# TIDA-010954-Power.net
KiCad netlist of a schematic drawn in Altium Designer
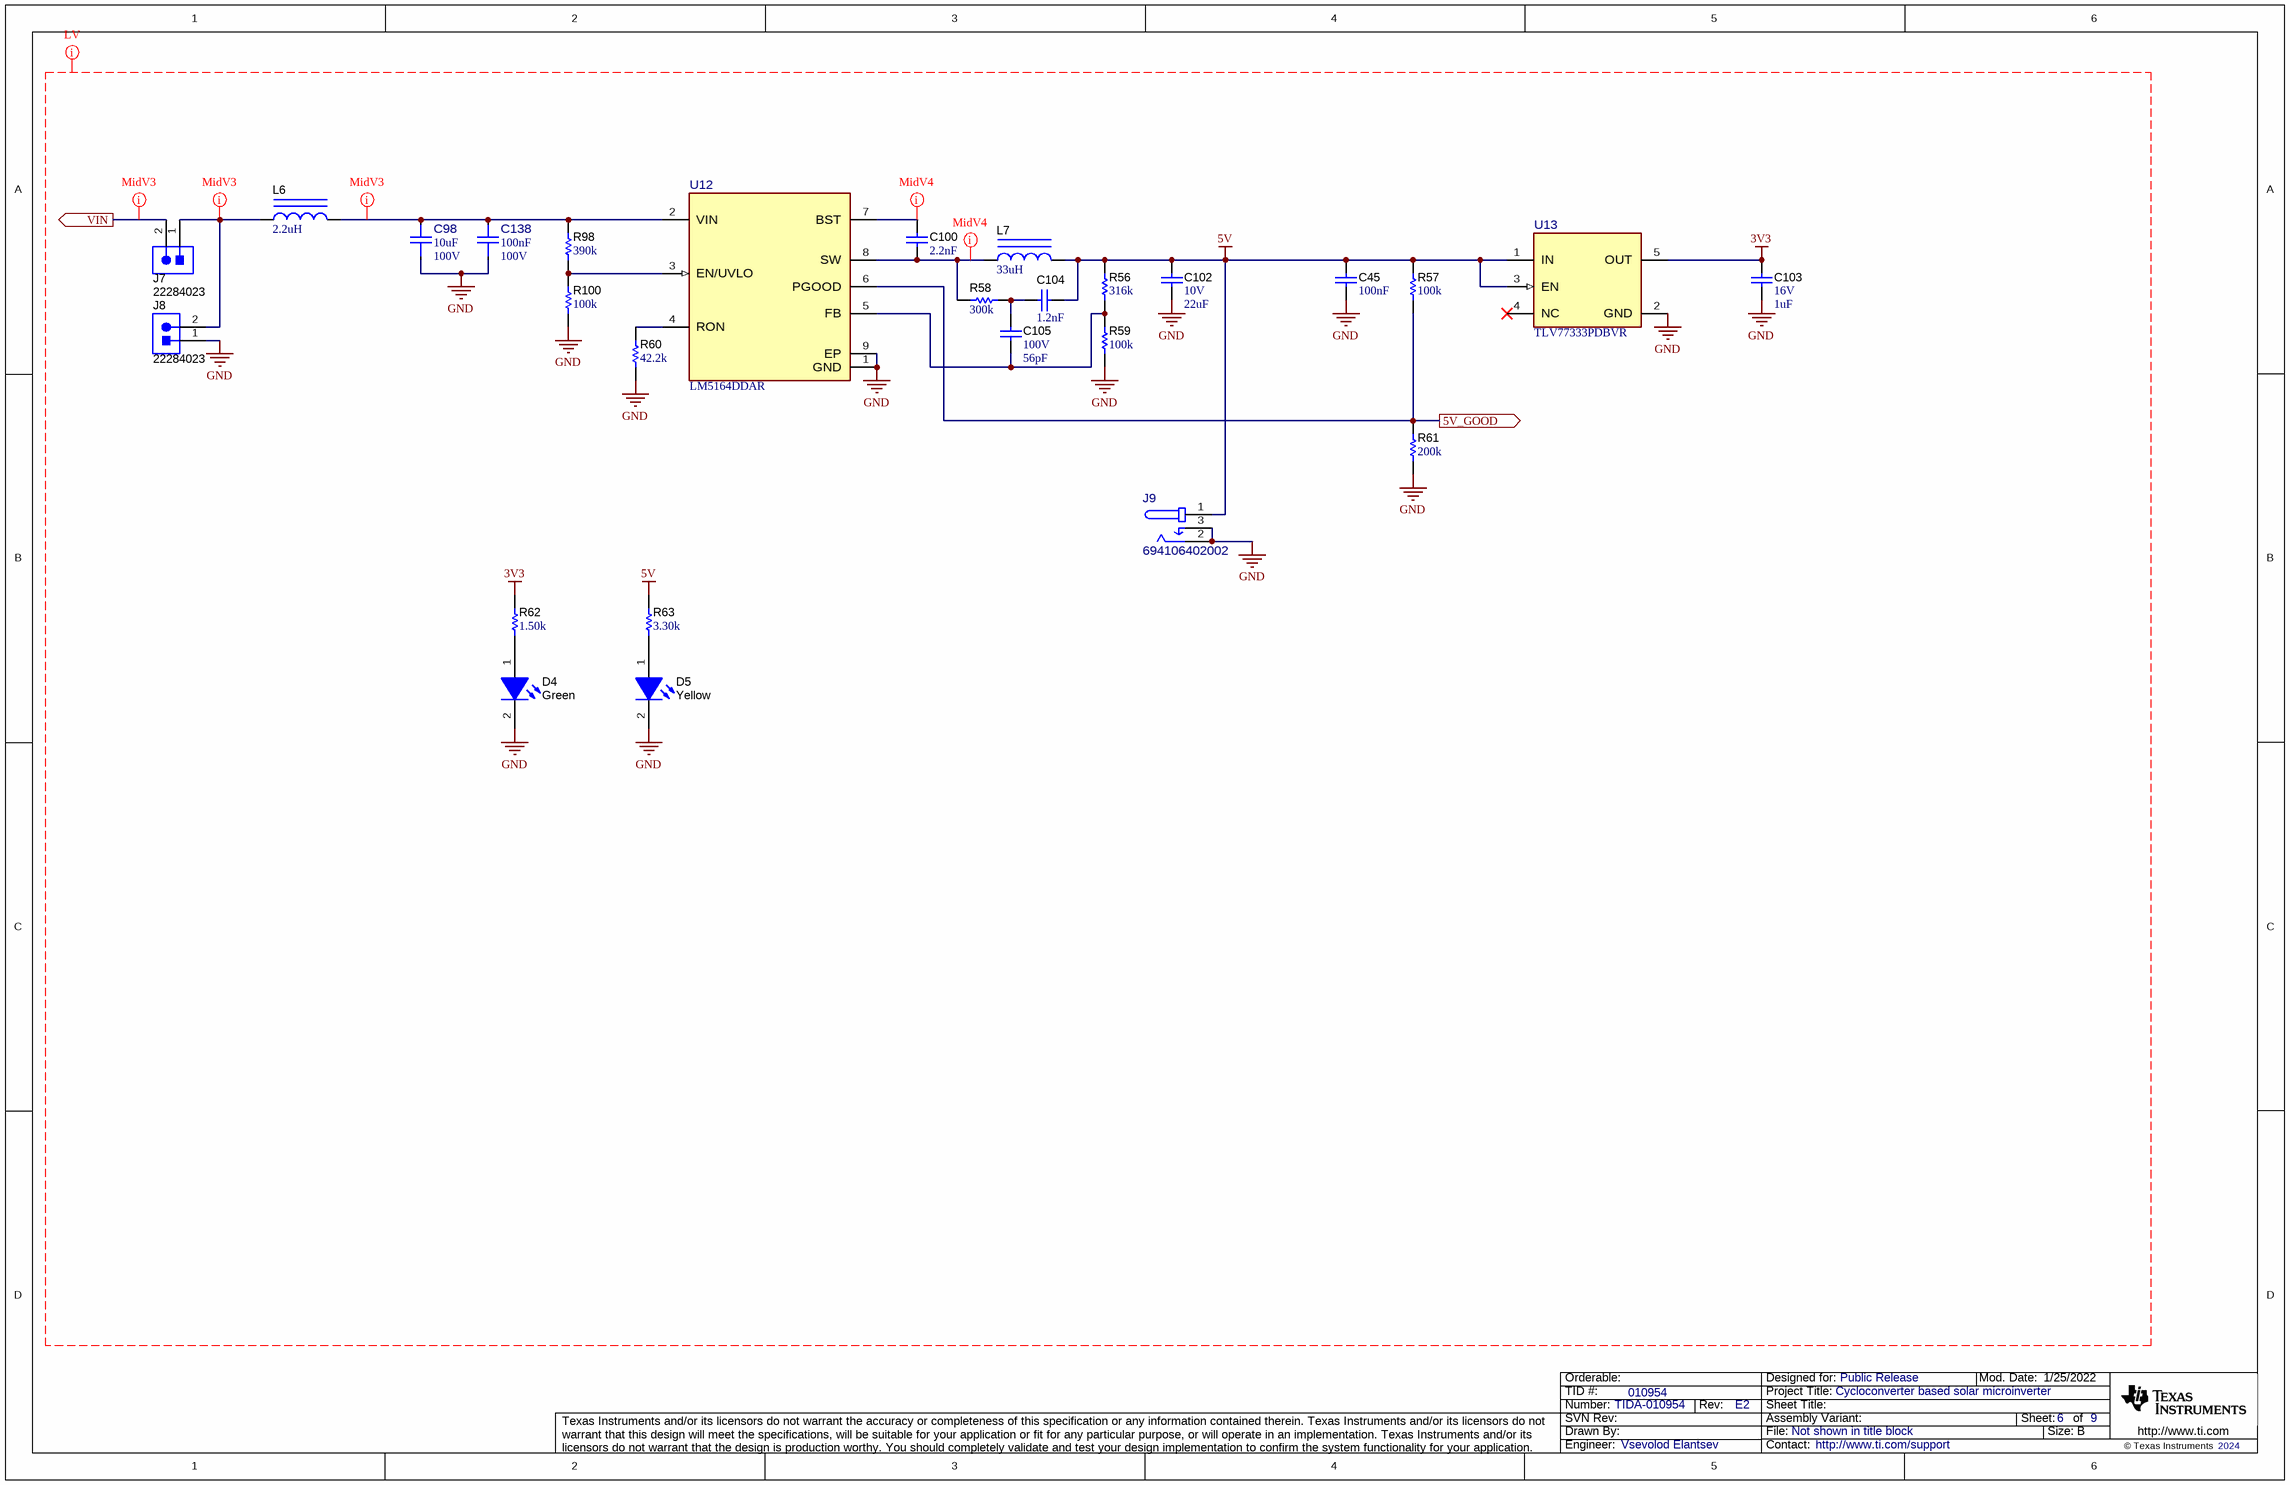
[diagram p0: TIDA-010954-Power.SchDoc]

(export (version "E")
  (design (tool "Eeschema 10.0.6"))
  (components
    (comp (ref "C45")
      (value "CGA3E2X7R1E104K080AA")
      (footprint "0603")
      (description "CAP, CERM, 0.1 uF, 25 V, +/- 10%, X7R, AEC-Q200 Grade 1, 0603")
      (fields
        (field (name "MANUFACTURER") "TDK")
        (field (name "CAP_F") "100nF")
        (field (name "PUBLISHER") "Texas Instruments")
      )
      (libsource (lib "Altium Vault - TI") (part "Capacitor"))
    )
    (comp (ref "C98")
      (value "GRM32EC72A106KE05L")
      (footprint "FP-GRM32EC72A106KE05L_1210-MFG")
      (description "10µF ±10% 100V Ceramic Capacitor X7S 1210 (3225 Metric)")
      (fields
        (field (name "VALUEDISPLAYED") "10uF")
        (field (name "MANUFACTURER") "Murata")
        (field (name "VDC_V") "100V")
      )
      (libsource (lib "Altium Vault - TI") (part "SYM-CC0402JRNPO9BN161"))
    )
    (comp (ref "C100")
      (value "C0603C222K5RAC")
      (footprint "0603")
      (description "CAP, CERM, 2200 pF, 50 V, +/- 10%, X7R, 0603")
      (fields
        (field (name "MANUFACTURER") "Kemet")
        (field (name "CAP_F") "2.2nF")
        (field (name "PUBLISHER") "Texas Instruments")
      )
      (libsource (lib "Altium Vault - TI") (part "Capacitor"))
    )
    (comp (ref "C102")
      (value "GRM31CR71A226KE15L")
      (footprint "1206_180")
      (description "CAP, CERM, 22 uF, 10 V, +/- 10%, X7R, 1206")
      (fields
        (field (name "MANUFACTURER") "MuRata")
        (field (name "VDC_V") "10V")
        (field (name "VALUEDISPLAYED") "22uF")
        (field (name "PUBLISHER") "Texas Instruments")
      )
      (libsource (lib "Altium Vault - TI") (part "Capacitor"))
    )
    (comp (ref "C103")
      (value "GRM185R61C105KE44D")
      (footprint "0603")
      (description "CAP, CERM, 1 uF, 16 V, +/- 10%, X5R, 0603")
      (fields
        (field (name "MANUFACTURER") "MuRata")
        (field (name "VDC_V") "16V")
        (field (name "VALUEDISPLAYED") "1uF")
        (field (name "PUBLISHER") "Texas Instruments")
      )
      (libsource (lib "Altium Vault - TI") (part "Capacitor"))
    )
    (comp (ref "C104")
      (value "GRM188R72A122KA01D")
      (footprint "0603")
      (description "CAP, CERM, 1200 pF, 100 V, +/- 10%, X7R, 0603")
      (fields
        (field (name "MANUFACTURER") "MuRata")
        (field (name "CAP_F") "1.2nF")
        (field (name "PUBLISHER") "Texas Instruments")
      )
      (libsource (lib "Altium Vault - TI") (part "Capacitor"))
    )
    (comp (ref "C105")
      (value "GRM1885C2A560JA01D")
      (footprint "0603")
      (description "CAP, CERM, 56 pF, 100 V, +/- 5%, C0G/NP0, 0603")
      (fields
        (field (name "MANUFACTURER") "MuRata")
        (field (name "VDC_V") "100V")
        (field (name "VALUEDISPLAYED") "56pF")
        (field (name "PUBLISHER") "Texas Instruments")
      )
      (libsource (lib "Altium Vault - TI") (part "Capacitor"))
    )
    (comp (ref "C138")
      (value "GRM188R72A104KA35J")
      (footprint "FP-GRM188R72A104KA35J_0603-MFG")
      (description "Chip Multilayer Ceramic Capacitors for General Purpose, 0603, 0.10uF, X7R, 15%, 10%, 100V")
      (fields
        (field (name "CAP_F") "100nF")
        (field (name "MANUFACTURER") "Murata")
        (field (name "VDC_V") "100V")
      )
      (libsource (lib "Altium Vault - TI") (part "SYM-GRM188R72A104KA35J"))
    )
    (comp (ref "D4")
      (value "Green")
      (footprint "APT1608_Green")
      (description "LED, Green, SMD")
      (fields (field (name "MANUFACTURER") "Kingbright") (field (name "PARTNUMBER") "APT1608MGC"))
      (libsource (lib "Altium Vault - TI") (part "LED"))
    )
    (comp (ref "D5")
      (value "Yellow")
      (footprint "APT1608_Yellow")
      (description "LED, Yellow, SMD")
      (fields (field (name "MANUFACTURER") "Kingbright") (field (name "PARTNUMBER") "APT1608SYCK"))
      (libsource (lib "Altium Vault - TI") (part "LED"))
    )
    (comp (ref "J7")
      (value "22284023")
      (footprint "Molex_0022284023")
      (description "Header, 2.54mm, 2x1, Tin, TH")
      (fields (field (name "MANUFACTURER") "Molex") (field (name "PUBLISHER") "Texas Instruments"))
      (libsource (lib "") (part "Header_2x1_1"))
    )
    (comp (ref "J8")
      (value "22284023")
      (footprint "Molex_0022284023")
      (description "Header, 2.54mm, 2x1, Tin, TH")
      (fields (field (name "MANUFACTURER") "Molex") (field (name "PUBLISHER") "Texas Instruments"))
      (libsource (lib "Altium Vault - TI") (part "Header_2x1"))
    )
    (comp (ref "J9")
      (value "694106402002")
      (footprint "FP-694106402002_CONN_PWR_10MM7_9MM0-MFG")
      (description "Power Barrel Connector Jack 2.10mm ID (0.083\"), 5.50mm OD (0.217\") Through Hole")
      (fields
        (field (name "MANUFACTURER") "Wurth Electronics")
        (field (name "DIGIKEY PART NUMBER") "732-5931-ND")
      )
      (libsource (lib "Altium Vault - TI") (part "SYM-694106402002"))
    )
    (comp (ref "L6")
      (value "LQM21PN2R2MGS")
      (footprint "0805_HV")
      (description "Inductor, Multilayer, Ferrite, 2.2 uH, 0.95 A, 0.18 ohm, SMD")
      (fields
        (field (name "MANUFACTURER") "MuRata")
        (field (name "VALUEDISPLAYED") "2.2uH")
        (field (name "PUBLISHER") "Texas Instruments")
      )
      (libsource (lib "Altium Vault - TI") (part "Inductor_Iron"))
    )
    (comp (ref "L7")
      (value "SRR1210-330M")
      (footprint "SRR1210")
      (description "Inductor, Drum Core, Ferrite, 33 uH, 3.7 A, 0.052 ohm, SMD")
      (fields
        (field (name "MANUFACTURER") "Bourns")
        (field (name "VALUEDISPLAYED") "33uH")
        (field (name "PUBLISHER") "Texas Instruments")
      )
      (libsource (lib "Altium Vault - TI") (part "Inductor_Iron"))
    )
    (comp (ref "R56")
      (value "RC0603FR-07316KL")
      (footprint "0603")
      (description "RES, 316 k, 1%, 0.1 W, 0603")
      (fields (field (name "MANUFACTURER") "Yageo") (field (name "VALUEDISPLAYED") "316k"))
      (libsource (lib "Altium Vault - TI") (part "Resistor"))
    )
    (comp (ref "R57")
      (value "RC0603FR-07100KL")
      (footprint "0603")
      (description "RES, 100 k, 1%, 0.1 W, 0603")
      (fields (field (name "MANUFACTURER") "Yageo") (field (name "VALUEDISPLAYED") "100k"))
      (libsource (lib "Altium Vault - TI") (part "Resistor"))
    )
    (comp (ref "R58")
      (value "CRCW0805300KJNEA")
      (footprint "0805_HV")
      (description "RES, 300 k, 5%, 0.125 W, AEC-Q200 Grade 0, 0805")
      (fields (field (name "MANUFACTURER") "Vishay-Dale") (field (name "VALUEDISPLAYED") "300k"))
      (libsource (lib "Altium Vault - TI") (part "Resistor"))
    )
    (comp (ref "R59")
      (value "RC0603FR-07100KL")
      (footprint "0603")
      (description "RES, 100 k, 1%, 0.1 W, 0603")
      (fields (field (name "MANUFACTURER") "Yageo") (field (name "VALUEDISPLAYED") "100k"))
      (libsource (lib "Altium Vault - TI") (part "Resistor"))
    )
    (comp (ref "R60")
      (value "RC0603FR-0742K2L")
      (footprint "0603")
      (description "RES, 42.2 k, 1%, 0.1 W, 0603")
      (fields (field (name "MANUFACTURER") "Yageo") (field (name "VALUEDISPLAYED") "42.2k"))
      (libsource (lib "Altium Vault - TI") (part "Resistor"))
    )
    (comp (ref "R61")
      (value "RC0603FR-07200KL")
      (footprint "0603")
      (description "RES, 200 k, 1%, 0.1 W, 0603")
      (fields (field (name "MANUFACTURER") "Yageo") (field (name "VALUEDISPLAYED") "200k"))
      (libsource (lib "Altium Vault - TI") (part "Resistor"))
    )
    (comp (ref "R62")
      (value "RC0603FR-071K5L")
      (footprint "0603")
      (description "RES, 1.50 k, 1%, 0.1 W, 0603")
      (fields (field (name "MANUFACTURER") "Yageo") (field (name "VALUEDISPLAYED") "1.50k"))
      (libsource (lib "Altium Vault - TI") (part "Resistor"))
    )
    (comp (ref "R63")
      (value "RC0603FR-073K3L")
      (footprint "0603")
      (description "RES, 3.30 k, 1%, 0.1 W, 0603")
      (fields (field (name "VALUEDISPLAYED") "3.30k") (field (name "MANUFACTURER") "Yageo"))
      (libsource (lib "Altium Vault - TI") (part "Resistor"))
    )
    (comp (ref "R98")
      (value "CRCW0805390KJNEA")
      (footprint "0805_HV")
      (description "RES, 390 k, 5%, 0.125 W, AEC-Q200 Grade 0, 0805")
      (fields (field (name "MANUFACTURER") "Vishay-Dale") (field (name "VALUEDISPLAYED") "390k"))
      (libsource (lib "Altium Vault - TI") (part "Resistor"))
    )
    (comp (ref "R100")
      (value "RC0603FR-07100KL")
      (footprint "0603")
      (description "RES, 100 k, 1%, 0.1 W, 0603")
      (fields (field (name "MANUFACTURER") "Yageo") (field (name "VALUEDISPLAYED") "100k"))
      (libsource (lib "Altium Vault - TI") (part "Resistor"))
    )
    (comp (ref "U12")
      (value "LM5164DDAR")
      (footprint "DDA0008E-MFG")
      (fields
        (field (name "PARTNUMBER") "LM5164DDAR")
        (field (name "MOUSER PART NUMBER") "595-LM5164DDAR")
        (field (name "MANUFACTURER") "Texas Instruments")
        (field (name "DIGIKEY PART NUMBER") "296-LM5164DDARCT-ND")
      )
      (libsource (lib "Altium Vault - TI") (part "SYM-LM5164DDAR"))
    )
    (comp (ref "U13")
      (value "TLV77333PDBVR")
      (footprint "DBV0005A-MFG")
      (description "300-mA, Small-Size, High-PSRR LDO")
      (fields (field (name "MANUFACTURER") "Texas Instruments") (field (name "PARTNUMBER") "TLV77333PDBVR"))
      (libsource (lib "Altium Vault - TI") (part "SYM-TLV77333PDBVR"))
    )
  )
  (nets
    (net (code "1") (name "/5V_GOOD") (class "Default")
      (node (ref "R57") (pin "1") (pinfunction "1_1") (pintype "passive"))
      (node (ref "R61") (pin "2") (pinfunction "2_2") (pintype "passive"))
      (node (ref "U12") (pin "6") (pinfunction "PGOOD_6") (pintype "open_collector"))
    )
    (net (code "2") (name "/VIN") (class "Default")
      (node (ref "J7") (pin "2") (pinfunction "2_2") (pintype "passive"))
    )
    (net (code "3") (name "3V3") (class "Default")
      (node (ref "C103") (pin "1") (pinfunction "1_1") (pintype "passive"))
      (node (ref "R62") (pin "2") (pinfunction "2_2") (pintype "passive"))
      (node (ref "U13") (pin "5") (pinfunction "OUT_5") (pintype "passive"))
    )
    (net (code "4") (name "5V") (class "Default")
      (node (ref "C102") (pin "1") (pinfunction "1_1") (pintype "passive"))
      (node (ref "C104") (pin "1") (pinfunction "1_1") (pintype "passive"))
      (node (ref "C45") (pin "2") (pinfunction "2_2") (pintype "passive"))
      (node (ref "J9") (pin "1") (pinfunction "1_1") (pintype "passive"))
      (node (ref "L7") (pin "2") (pinfunction "2_2") (pintype "passive"))
      (node (ref "R56") (pin "2") (pinfunction "2_2") (pintype "passive"))
      (node (ref "R57") (pin "2") (pinfunction "2_2") (pintype "passive"))
      (node (ref "R63") (pin "2") (pinfunction "2_2") (pintype "passive"))
      (node (ref "U13") (pin "1") (pinfunction "IN_1") (pintype "power_in"))
      (node (ref "U13") (pin "3") (pinfunction "EN_3") (pintype "input"))
    )
    (net (code "5") (name "GND") (class "Default")
      (node (ref "C102") (pin "2") (pinfunction "2_2") (pintype "passive"))
      (node (ref "C103") (pin "2") (pinfunction "2_2") (pintype "passive"))
      (node (ref "C138") (pin "1") (pinfunction "1_1") (pintype "passive"))
      (node (ref "C45") (pin "1") (pinfunction "1_1") (pintype "passive"))
      (node (ref "C98") (pin "1") (pinfunction "1_1") (pintype "passive"))
      (node (ref "D4") (pin "2") (pinfunction "K_2") (pintype "passive"))
      (node (ref "D5") (pin "2") (pinfunction "K_2") (pintype "passive"))
      (node (ref "J8") (pin "1") (pinfunction "1_1") (pintype "passive"))
      (node (ref "J9") (pin "2") (pinfunction "2_2") (pintype "passive"))
      (node (ref "J9") (pin "3") (pinfunction "3_3") (pintype "passive"))
      (node (ref "R100") (pin "1") (pinfunction "1_1") (pintype "passive"))
      (node (ref "R59") (pin "1") (pinfunction "1_1") (pintype "passive"))
      (node (ref "R60") (pin "1") (pinfunction "1_1") (pintype "passive"))
      (node (ref "R61") (pin "1") (pinfunction "1_1") (pintype "passive"))
      (node (ref "U12") (pin "1") (pinfunction "GND_1") (pintype "power_in"))
      (node (ref "U12") (pin "9") (pinfunction "EP_9") (pintype "passive"))
      (node (ref "U13") (pin "2") (pinfunction "GND_2") (pintype "power_in"))
    )
    (net (code "6") (name "Net-(C104-Pad2)") (class "Default")
      (node (ref "C104") (pin "2") (pinfunction "2_2") (pintype "passive"))
      (node (ref "C105") (pin "1") (pinfunction "1_1") (pintype "passive"))
      (node (ref "R58") (pin "2") (pinfunction "2_2") (pintype "passive"))
    )
    (net (code "7") (name "Net-(D4-A)") (class "Default")
      (node (ref "D4") (pin "1") (pinfunction "A_1") (pintype "passive"))
      (node (ref "R62") (pin "1") (pinfunction "1_1") (pintype "passive"))
    )
    (net (code "8") (name "Net-(D5-A)") (class "Default")
      (node (ref "D5") (pin "1") (pinfunction "A_1") (pintype "passive"))
      (node (ref "R63") (pin "1") (pinfunction "1_1") (pintype "passive"))
    )
    (net (code "9") (name "Net-(J7-Pad1)") (class "Default")
      (node (ref "J7") (pin "1") (pinfunction "1_1") (pintype "passive"))
      (node (ref "J8") (pin "2") (pinfunction "2_2") (pintype "passive"))
      (node (ref "L6") (pin "1") (pinfunction "1_1") (pintype "passive"))
    )
    (net (code "10") (name "Net-(U12-BST)") (class "Default")
      (node (ref "C100") (pin "1") (pinfunction "1_1") (pintype "passive"))
      (node (ref "U12") (pin "7") (pinfunction "BST_7") (pintype "passive"))
    )
    (net (code "11") (name "Net-(U12-EN{slash}UVLO)") (class "Default")
      (node (ref "R100") (pin "2") (pinfunction "2_2") (pintype "passive"))
      (node (ref "R98") (pin "1") (pinfunction "1_1") (pintype "passive"))
      (node (ref "U12") (pin "3") (pinfunction "EN/UVLO_3") (pintype "input"))
    )
    (net (code "12") (name "Net-(U12-FB)") (class "Default")
      (node (ref "C105") (pin "2") (pinfunction "2_2") (pintype "passive"))
      (node (ref "R56") (pin "1") (pinfunction "1_1") (pintype "passive"))
      (node (ref "R59") (pin "2") (pinfunction "2_2") (pintype "passive"))
      (node (ref "U12") (pin "5") (pinfunction "FB_5") (pintype "passive"))
    )
    (net (code "13") (name "Net-(U12-RON)") (class "Default")
      (node (ref "R60") (pin "2") (pinfunction "2_2") (pintype "passive"))
      (node (ref "U12") (pin "4") (pinfunction "RON_4") (pintype "passive"))
    )
    (net (code "14") (name "Net-(U12-SW)") (class "Default")
      (node (ref "C100") (pin "2") (pinfunction "2_2") (pintype "passive"))
      (node (ref "L7") (pin "1") (pinfunction "1_1") (pintype "passive"))
      (node (ref "R58") (pin "1") (pinfunction "1_1") (pintype "passive"))
      (node (ref "U12") (pin "8") (pinfunction "SW_8") (pintype "passive"))
    )
    (net (code "15") (name "Net-(U12-VIN)") (class "Default")
      (node (ref "C138") (pin "2") (pinfunction "2_2") (pintype "passive"))
      (node (ref "C98") (pin "2") (pinfunction "2_2") (pintype "passive"))
      (node (ref "L6") (pin "2") (pinfunction "2_2") (pintype "passive"))
      (node (ref "R98") (pin "2") (pinfunction "2_2") (pintype "passive"))
      (node (ref "U12") (pin "2") (pinfunction "VIN_2") (pintype "power_in"))
    )
    (net (code "16") (name "unconnected-(U13-NC-Pad4)") (class "Default")
      (node (ref "U13") (pin "4") (pinfunction "NC_4") (pintype "passive+no_connect"))
    )
  )
)
